# 3__Output_Feedback.net
KiCad netlist of a schematic drawn in Altium Designer
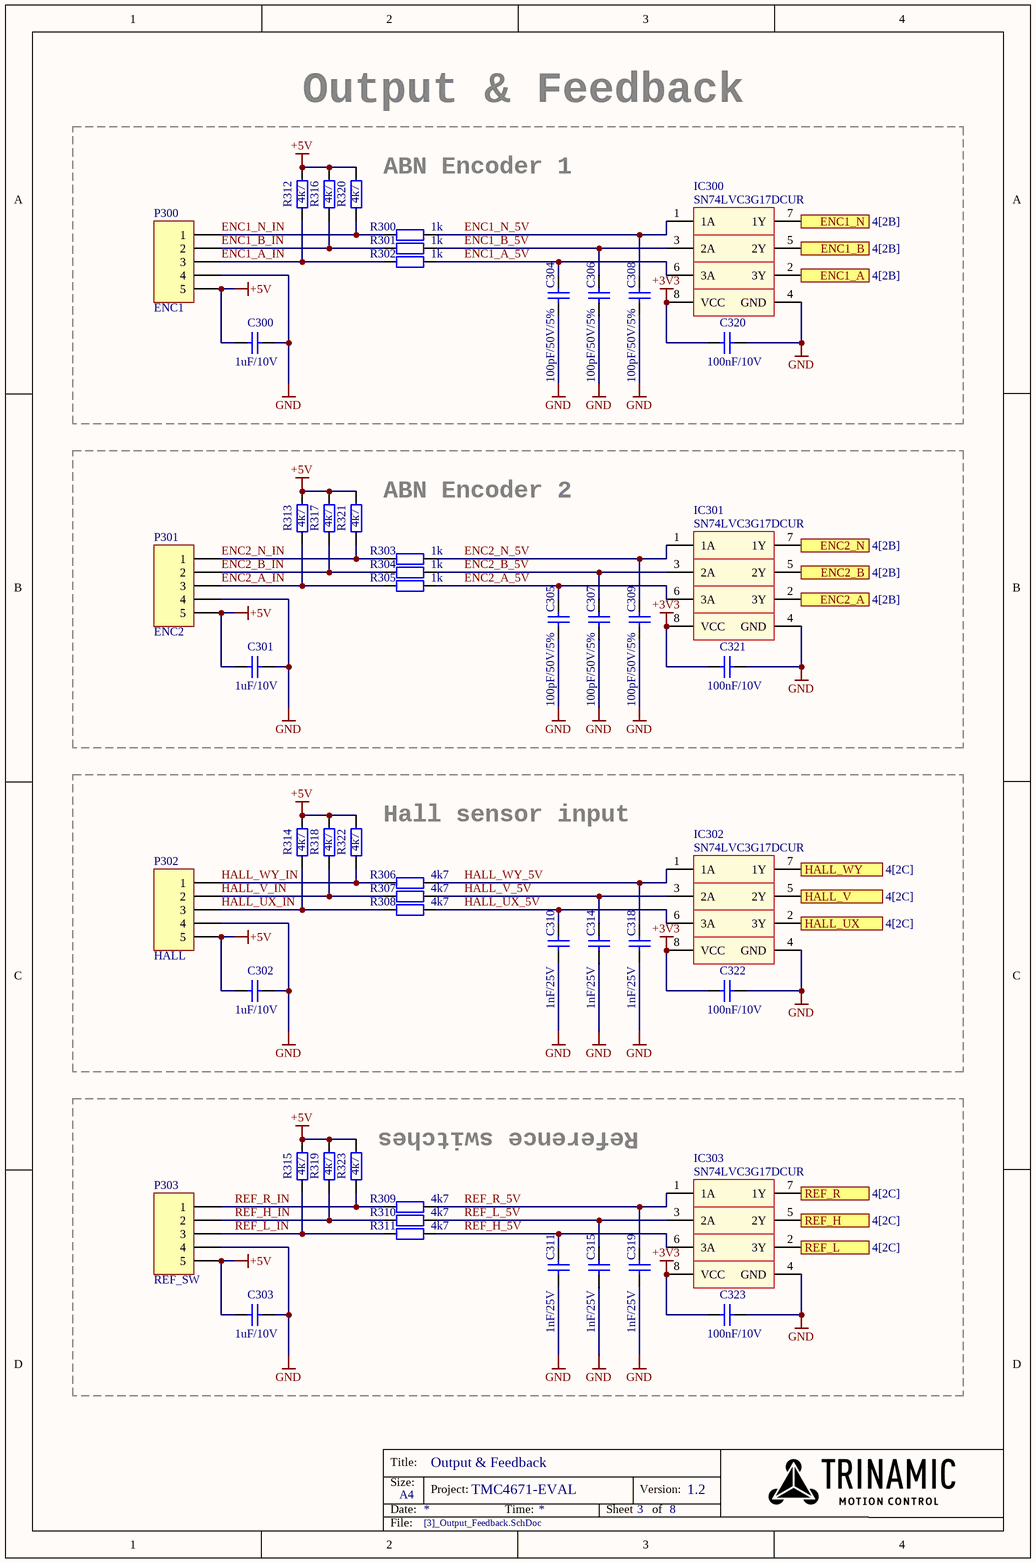
[diagram p0: [3]_Output_Feedback.SchDoc]

(export (version "E")
  (design (tool "Eeschema 10.0.6"))
  (components
    (comp (ref "C300")
      (value "1uF/10V")
      (footprint "C0603")
      (description "SMD Multilayer Ceramic Capacitor, 0603 [1608 Metric], 1 µF, 10 V, ± 10%, X5R, MC Series")
      (fields (field (name "MF") "MULTICOMP") (field (name "MPN") "MC0603X105K100CT"))
      (libsource (lib "SMD_Passives") (part "C, 1 µF, 10 V, ± 10%, X5R, MC Series, 0603 [1608 Metric]"))
    )
    (comp (ref "C301")
      (value "1uF/10V")
      (footprint "C0603")
      (description "SMD Multilayer Ceramic Capacitor, 0603 [1608 Metric], 1 µF, 10 V, ± 10%, X5R, MC Series")
      (fields (field (name "MF") "MULTICOMP") (field (name "MPN") "MC0603X105K100CT"))
      (libsource (lib "SMD_Passives") (part "C, 1 µF, 10 V, ± 10%, X5R, MC Series, 0603 [1608 Metric]"))
    )
    (comp (ref "C302")
      (value "1uF/10V")
      (footprint "C0603")
      (description "SMD Multilayer Ceramic Capacitor, 0603 [1608 Metric], 1 µF, 10 V, ± 10%, X5R, MC Series")
      (fields (field (name "MF") "MULTICOMP") (field (name "MPN") "MC0603X105K100CT"))
      (libsource (lib "SMD_Passives") (part "C, 1 µF, 10 V, ± 10%, X5R, MC Series, 0603 [1608 Metric]"))
    )
    (comp (ref "C303")
      (value "1uF/10V")
      (footprint "C0603")
      (description "SMD Multilayer Ceramic Capacitor, 0603 [1608 Metric], 1 µF, 10 V, ± 10%, X5R, MC Series")
      (fields (field (name "MF") "MULTICOMP") (field (name "MPN") "MC0603X105K100CT"))
      (libsource (lib "SMD_Passives") (part "C, 1 µF, 10 V, ± 10%, X5R, MC Series, 0603 [1608 Metric]"))
    )
    (comp (ref "C304")
      (value "100pF/50V/5%")
      (footprint "C0603")
      (description "SMD Multilayer Ceramic Capacitor, 0603 [1608 Metric], 100 pF, 50 V, ± 5%, C0G / NP0, MC Series")
      (fields (field (name "MF") "MULTICOMP") (field (name "MPN") "MC0603N101J500CT"))
      (libsource (lib "SMD_Passives") (part "C, 100 pF, 50 V, ± 5%, C0G / NP0, MC Series, 0603 [1608 Metric]"))
    )
    (comp (ref "C305")
      (value "100pF/50V/5%")
      (footprint "C0603")
      (description "SMD Multilayer Ceramic Capacitor, 0603 [1608 Metric], 100 pF, 50 V, ± 5%, C0G / NP0, MC Series")
      (fields (field (name "MF") "MULTICOMP") (field (name "MPN") "MC0603N101J500CT"))
      (libsource (lib "SMD_Passives") (part "C, 100 pF, 50 V, ± 5%, C0G / NP0, MC Series, 0603 [1608 Metric]"))
    )
    (comp (ref "C306")
      (value "100pF/50V/5%")
      (footprint "C0603")
      (description "SMD Multilayer Ceramic Capacitor, 0603 [1608 Metric], 100 pF, 50 V, ± 5%, C0G / NP0, MC Series")
      (fields (field (name "MF") "MULTICOMP") (field (name "MPN") "MC0603N101J500CT"))
      (libsource (lib "SMD_Passives") (part "C, 100 pF, 50 V, ± 5%, C0G / NP0, MC Series, 0603 [1608 Metric]"))
    )
    (comp (ref "C307")
      (value "100pF/50V/5%")
      (footprint "C0603")
      (description "SMD Multilayer Ceramic Capacitor, 0603 [1608 Metric], 100 pF, 50 V, ± 5%, C0G / NP0, MC Series")
      (fields (field (name "MF") "MULTICOMP") (field (name "MPN") "MC0603N101J500CT"))
      (libsource (lib "SMD_Passives") (part "C, 100 pF, 50 V, ± 5%, C0G / NP0, MC Series, 0603 [1608 Metric]"))
    )
    (comp (ref "C308")
      (value "100pF/50V/5%")
      (footprint "C0603")
      (description "SMD Multilayer Ceramic Capacitor, 0603 [1608 Metric], 100 pF, 50 V, ± 5%, C0G / NP0, MC Series")
      (fields (field (name "MF") "MULTICOMP") (field (name "MPN") "MC0603N101J500CT"))
      (libsource (lib "SMD_Passives") (part "C, 100 pF, 50 V, ± 5%, C0G / NP0, MC Series, 0603 [1608 Metric]"))
    )
    (comp (ref "C309")
      (value "100pF/50V/5%")
      (footprint "C0603")
      (description "SMD Multilayer Ceramic Capacitor, 0603 [1608 Metric], 100 pF, 50 V, ± 5%, C0G / NP0, MC Series")
      (fields (field (name "MF") "MULTICOMP") (field (name "MPN") "MC0603N101J500CT"))
      (libsource (lib "SMD_Passives") (part "C, 100 pF, 50 V, ± 5%, C0G / NP0, MC Series, 0603 [1608 Metric]"))
    )
    (comp (ref "C310")
      (value "1nF/25V")
      (footprint "C0603")
      (description "SMD Multilayer Ceramic Capacitor, 0603 [1608 Metric], 1000 pF, 25 V, ± 10%, X7R, MC Series")
      (fields (field (name "MF") "MULTICOMP") (field (name "MPN") "MC0603B102K250CT"))
      (libsource (lib "SMD_Passives") (part "C, 1nF, 25 V, ± 10%, X7R, MC Series, 0603 [1608 Metric]"))
    )
    (comp (ref "C311")
      (value "1nF/25V")
      (footprint "C0603")
      (description "SMD Multilayer Ceramic Capacitor, 0603 [1608 Metric], 1000 pF, 25 V, ± 10%, X7R, MC Series")
      (fields (field (name "MF") "MULTICOMP") (field (name "MPN") "MC0603B102K250CT"))
      (libsource (lib "SMD_Passives") (part "C, 1nF, 25 V, ± 10%, X7R, MC Series, 0603 [1608 Metric]"))
    )
    (comp (ref "C314")
      (value "1nF/25V")
      (footprint "C0603")
      (description "SMD Multilayer Ceramic Capacitor, 0603 [1608 Metric], 1000 pF, 25 V, ± 10%, X7R, MC Series")
      (fields (field (name "MF") "MULTICOMP") (field (name "MPN") "MC0603B102K250CT"))
      (libsource (lib "SMD_Passives") (part "C, 1nF, 25 V, ± 10%, X7R, MC Series, 0603 [1608 Metric]"))
    )
    (comp (ref "C315")
      (value "1nF/25V")
      (footprint "C0603")
      (description "SMD Multilayer Ceramic Capacitor, 0603 [1608 Metric], 1000 pF, 25 V, ± 10%, X7R, MC Series")
      (fields (field (name "MF") "MULTICOMP") (field (name "MPN") "MC0603B102K250CT"))
      (libsource (lib "SMD_Passives") (part "C, 1nF, 25 V, ± 10%, X7R, MC Series, 0603 [1608 Metric]"))
    )
    (comp (ref "C318")
      (value "1nF/25V")
      (footprint "C0603")
      (description "SMD Multilayer Ceramic Capacitor, 0603 [1608 Metric], 1000 pF, 25 V, ± 10%, X7R, MC Series")
      (fields (field (name "MF") "MULTICOMP") (field (name "MPN") "MC0603B102K250CT"))
      (libsource (lib "SMD_Passives") (part "C, 1nF, 25 V, ± 10%, X7R, MC Series, 0603 [1608 Metric]"))
    )
    (comp (ref "C319")
      (value "1nF/25V")
      (footprint "C0603")
      (description "SMD Multilayer Ceramic Capacitor, 0603 [1608 Metric], 1000 pF, 25 V, ± 10%, X7R, MC Series")
      (fields (field (name "MF") "MULTICOMP") (field (name "MPN") "MC0603B102K250CT"))
      (libsource (lib "SMD_Passives") (part "C, 1nF, 25 V, ± 10%, X7R, MC Series, 0603 [1608 Metric]"))
    )
    (comp (ref "C320")
      (value "100nF/10V")
      (footprint "C0603")
      (description "SMD Multilayer Ceramic Capacitor, 0603 [1608 Metric], 0.1 µF, 10 V, ± 10%, X7R, MC Series")
      (fields (field (name "MF") "Multicomp") (field (name "MPN") "MC0603B104K100CT"))
      (libsource (lib "SMD_Passives") (part "C, 0.1 µF, 10 V, ± 10%, X7R, 0603"))
    )
    (comp (ref "C321")
      (value "100nF/10V")
      (footprint "C0603")
      (description "SMD Multilayer Ceramic Capacitor, 0603 [1608 Metric], 0.1 µF, 10 V, ± 10%, X7R, MC Series")
      (fields (field (name "MF") "Multicomp") (field (name "MPN") "MC0603B104K100CT"))
      (libsource (lib "SMD_Passives") (part "C, 0.1 µF, 10 V, ± 10%, X7R, 0603"))
    )
    (comp (ref "C322")
      (value "100nF/10V")
      (footprint "C0603")
      (description "SMD Multilayer Ceramic Capacitor, 0603 [1608 Metric], 0.1 µF, 10 V, ± 10%, X7R, MC Series")
      (fields (field (name "MF") "Multicomp") (field (name "MPN") "MC0603B104K100CT"))
      (libsource (lib "SMD_Passives") (part "C, 0.1 µF, 10 V, ± 10%, X7R, 0603"))
    )
    (comp (ref "C323")
      (value "100nF/10V")
      (footprint "C0603")
      (description "SMD Multilayer Ceramic Capacitor, 0603 [1608 Metric], 0.1 µF, 10 V, ± 10%, X7R, MC Series")
      (fields (field (name "MF") "Multicomp") (field (name "MPN") "MC0603B104K100CT"))
      (libsource (lib "SMD_Passives") (part "C, 0.1 µF, 10 V, ± 10%, X7R, 0603"))
    )
    (comp (ref "IC300")
      (value "SN74LVC3G17DCUR")
      (footprint "TSSOP50P310X90-8L")
      (description "Triple Schmitt-Trigger Buffer, 74LVC3G17, 1.65 V to 5.5 V, VSSOP-8")
      (fields (field (name "MF") "TEXAS INSTRUMENTS"))
      (libsource (lib "TMC4671-EVAL_V1_0") (part "SN74LVC3G17DCUR"))
    )
    (comp (ref "IC301")
      (value "SN74LVC3G17DCUR")
      (footprint "TSSOP50P310X90-8L")
      (description "Triple Schmitt-Trigger Buffer, 74LVC3G17, 1.65 V to 5.5 V, VSSOP-8")
      (fields (field (name "MF") "TEXAS INSTRUMENTS"))
      (libsource (lib "TMC4671-EVAL_V1_0") (part "SN74LVC3G17DCUR"))
    )
    (comp (ref "IC302")
      (value "SN74LVC3G17DCUR")
      (footprint "TSSOP50P310X90-8L")
      (description "Triple Schmitt-Trigger Buffer, 74LVC3G17, 1.65 V to 5.5 V, VSSOP-8")
      (fields (field (name "MF") "TEXAS INSTRUMENTS"))
      (libsource (lib "TMC4671-EVAL_V1_0") (part "SN74LVC3G17DCUR"))
    )
    (comp (ref "IC303")
      (value "SN74LVC3G17DCUR")
      (footprint "TSSOP50P310X90-8L")
      (description "Triple Schmitt-Trigger Buffer, 74LVC3G17, 1.65 V to 5.5 V, VSSOP-8")
      (fields (field (name "MF") "TEXAS INSTRUMENTS"))
      (libsource (lib "TMC4671-EVAL_V1_0") (part "SN74LVC3G17DCUR"))
    )
    (comp (ref "P300")
      (value "ENC1")
      (footprint "TH_HDR_1X5")
      (description "Header, 5-Pin")
      (libsource (lib "Miscellaneous Connectors") (part "Header 5"))
    )
    (comp (ref "P301")
      (value "ENC2")
      (footprint "TH_HDR_1X5")
      (description "Header, 5-Pin")
      (libsource (lib "Miscellaneous Connectors") (part "Header 5"))
    )
    (comp (ref "P302")
      (value "HALL")
      (footprint "TH_HDR_1X5")
      (description "Header, 5-Pin")
      (libsource (lib "Miscellaneous Connectors") (part "Header 5"))
    )
    (comp (ref "P303")
      (value "REF_SW")
      (footprint "TH_HDR_1X5")
      (description "Header, 5-Pin")
      (libsource (lib "Miscellaneous Connectors") (part "Header 5"))
    )
    (comp (ref "R300")
      (value "1k")
      (footprint "R0603")
      (description "SMD Chip Resistor, Thick Film, 1 kohm, 50 V, 0603 [1608 Metric], 100 mW, ± 1%, MCWR Series")
      (fields
        (field (name "MPN") "MCWR06X1001FTL")
        (field (name "MF") "MULTICOMP")
        (field (name "RESISTANCE") "1k")
      )
      (libsource (lib "SMD_Passives") (part "R, 1 kohm, 50 V, 0603 [1608 Metric], 100mW, ± 1%, MCWR Series"))
    )
    (comp (ref "R301")
      (value "1k")
      (footprint "R0603")
      (description "SMD Chip Resistor, Thick Film, 1 kohm, 50 V, 0603 [1608 Metric], 100 mW, ± 1%, MCWR Series")
      (fields
        (field (name "MPN") "MCWR06X1001FTL")
        (field (name "MF") "MULTICOMP")
        (field (name "RESISTANCE") "1k")
      )
      (libsource (lib "SMD_Passives") (part "R, 1 kohm, 50 V, 0603 [1608 Metric], 100mW, ± 1%, MCWR Series"))
    )
    (comp (ref "R302")
      (value "1k")
      (footprint "R0603")
      (description "SMD Chip Resistor, Thick Film, 1 kohm, 50 V, 0603 [1608 Metric], 100 mW, ± 1%, MCWR Series")
      (fields
        (field (name "MPN") "MCWR06X1001FTL")
        (field (name "MF") "MULTICOMP")
        (field (name "RESISTANCE") "1k")
      )
      (libsource (lib "SMD_Passives") (part "R, 1 kohm, 50 V, 0603 [1608 Metric], 100mW, ± 1%, MCWR Series"))
    )
    (comp (ref "R303")
      (value "1k")
      (footprint "R0603")
      (description "SMD Chip Resistor, Thick Film, 1 kohm, 50 V, 0603 [1608 Metric], 100 mW, ± 1%, MCWR Series")
      (fields
        (field (name "MPN") "MCWR06X1001FTL")
        (field (name "MF") "MULTICOMP")
        (field (name "RESISTANCE") "1k")
      )
      (libsource (lib "SMD_Passives") (part "R, 1 kohm, 50 V, 0603 [1608 Metric], 100mW, ± 1%, MCWR Series"))
    )
    (comp (ref "R304")
      (value "1k")
      (footprint "R0603")
      (description "SMD Chip Resistor, Thick Film, 1 kohm, 50 V, 0603 [1608 Metric], 100 mW, ± 1%, MCWR Series")
      (fields
        (field (name "MPN") "MCWR06X1001FTL")
        (field (name "MF") "MULTICOMP")
        (field (name "RESISTANCE") "1k")
      )
      (libsource (lib "SMD_Passives") (part "R, 1 kohm, 50 V, 0603 [1608 Metric], 100mW, ± 1%, MCWR Series"))
    )
    (comp (ref "R305")
      (value "1k")
      (footprint "R0603")
      (description "SMD Chip Resistor, Thick Film, 1 kohm, 50 V, 0603 [1608 Metric], 100 mW, ± 1%, MCWR Series")
      (fields
        (field (name "MPN") "MCWR06X1001FTL")
        (field (name "MF") "MULTICOMP")
        (field (name "RESISTANCE") "1k")
      )
      (libsource (lib "SMD_Passives") (part "R, 1 kohm, 50 V, 0603 [1608 Metric], 100mW, ± 1%, MCWR Series"))
    )
    (comp (ref "R306")
      (value "4k7")
      (footprint "R0603")
      (description "SMD Chip Resistor, 4.7 kohm, 75 V, 0603 [1608 Metric], 100 mW, ± 1%, WR06 Series")
      (fields
        (field (name "MPN") "WR06X4701FTL")
        (field (name "MF") "WALSIN")
        (field (name "RESISTANCE") "4k7")
      )
      (libsource (lib "SMD_Passives") (part "R, 4.7 kohm, 75 V, 0603 [1608 Metric], 100 mW, ± 1%, WR06 Series"))
    )
    (comp (ref "R307")
      (value "4k7")
      (footprint "R0603")
      (description "SMD Chip Resistor, 4.7 kohm, 75 V, 0603 [1608 Metric], 100 mW, ± 1%, WR06 Series")
      (fields
        (field (name "MPN") "WR06X4701FTL")
        (field (name "MF") "WALSIN")
        (field (name "RESISTANCE") "4k7")
      )
      (libsource (lib "SMD_Passives") (part "R, 4.7 kohm, 75 V, 0603 [1608 Metric], 100 mW, ± 1%, WR06 Series"))
    )
    (comp (ref "R308")
      (value "4k7")
      (footprint "R0603")
      (description "SMD Chip Resistor, 4.7 kohm, 75 V, 0603 [1608 Metric], 100 mW, ± 1%, WR06 Series")
      (fields
        (field (name "MPN") "WR06X4701FTL")
        (field (name "MF") "WALSIN")
        (field (name "RESISTANCE") "4k7")
      )
      (libsource (lib "SMD_Passives") (part "R, 4.7 kohm, 75 V, 0603 [1608 Metric], 100 mW, ± 1%, WR06 Series"))
    )
    (comp (ref "R309")
      (value "4k7")
      (footprint "R0603")
      (description "SMD Chip Resistor, 4.7 kohm, 75 V, 0603 [1608 Metric], 100 mW, ± 1%, WR06 Series")
      (fields
        (field (name "MPN") "WR06X4701FTL")
        (field (name "MF") "WALSIN")
        (field (name "RESISTANCE") "4k7")
      )
      (libsource (lib "SMD_Passives") (part "R, 4.7 kohm, 75 V, 0603 [1608 Metric], 100 mW, ± 1%, WR06 Series"))
    )
    (comp (ref "R310")
      (value "4k7")
      (footprint "R0603")
      (description "SMD Chip Resistor, 4.7 kohm, 75 V, 0603 [1608 Metric], 100 mW, ± 1%, WR06 Series")
      (fields
        (field (name "MPN") "WR06X4701FTL")
        (field (name "MF") "WALSIN")
        (field (name "RESISTANCE") "4k7")
      )
      (libsource (lib "SMD_Passives") (part "R, 4.7 kohm, 75 V, 0603 [1608 Metric], 100 mW, ± 1%, WR06 Series"))
    )
    (comp (ref "R311")
      (value "4k7")
      (footprint "R0603")
      (description "SMD Chip Resistor, 4.7 kohm, 75 V, 0603 [1608 Metric], 100 mW, ± 1%, WR06 Series")
      (fields
        (field (name "MPN") "WR06X4701FTL")
        (field (name "MF") "WALSIN")
        (field (name "RESISTANCE") "4k7")
      )
      (libsource (lib "SMD_Passives") (part "R, 4.7 kohm, 75 V, 0603 [1608 Metric], 100 mW, ± 1%, WR06 Series"))
    )
    (comp (ref "R312")
      (value "4k7")
      (footprint "R0603")
      (description "SMD Chip Resistor, 4.7 kohm, 75 V, 0603 [1608 Metric], 100 mW, ± 1%, WR06 Series")
      (fields
        (field (name "MPN") "WR06X4701FTL")
        (field (name "MF") "WALSIN")
        (field (name "RESISTANCE") "4k7")
      )
      (libsource (lib "") (part "R, 4.7 kohm, 75 V, 0603 [1608 Metric], 100 mW, ± 1%, WR06 Series_1"))
    )
    (comp (ref "R313")
      (value "4k7")
      (footprint "R0603")
      (description "SMD Chip Resistor, 4.7 kohm, 75 V, 0603 [1608 Metric], 100 mW, ± 1%, WR06 Series")
      (fields
        (field (name "MPN") "WR06X4701FTL")
        (field (name "MF") "WALSIN")
        (field (name "RESISTANCE") "4k7")
      )
      (libsource (lib "") (part "R, 4.7 kohm, 75 V, 0603 [1608 Metric], 100 mW, ± 1%, WR06 Series_1"))
    )
    (comp (ref "R314")
      (value "4k7")
      (footprint "R0603")
      (description "SMD Chip Resistor, 4.7 kohm, 75 V, 0603 [1608 Metric], 100 mW, ± 1%, WR06 Series")
      (fields
        (field (name "MPN") "WR06X4701FTL")
        (field (name "MF") "WALSIN")
        (field (name "RESISTANCE") "4k7")
      )
      (libsource (lib "") (part "R, 4.7 kohm, 75 V, 0603 [1608 Metric], 100 mW, ± 1%, WR06 Series_1"))
    )
    (comp (ref "R315")
      (value "4k7")
      (footprint "R0603")
      (description "SMD Chip Resistor, 4.7 kohm, 75 V, 0603 [1608 Metric], 100 mW, ± 1%, WR06 Series")
      (fields
        (field (name "MPN") "WR06X4701FTL")
        (field (name "MF") "WALSIN")
        (field (name "RESISTANCE") "4k7")
      )
      (libsource (lib "") (part "R, 4.7 kohm, 75 V, 0603 [1608 Metric], 100 mW, ± 1%, WR06 Series_1"))
    )
    (comp (ref "R316")
      (value "4k7")
      (footprint "R0603")
      (description "SMD Chip Resistor, 4.7 kohm, 75 V, 0603 [1608 Metric], 100 mW, ± 1%, WR06 Series")
      (fields
        (field (name "MPN") "WR06X4701FTL")
        (field (name "MF") "WALSIN")
        (field (name "RESISTANCE") "4k7")
      )
      (libsource (lib "") (part "R, 4.7 kohm, 75 V, 0603 [1608 Metric], 100 mW, ± 1%, WR06 Series_1"))
    )
    (comp (ref "R317")
      (value "4k7")
      (footprint "R0603")
      (description "SMD Chip Resistor, 4.7 kohm, 75 V, 0603 [1608 Metric], 100 mW, ± 1%, WR06 Series")
      (fields
        (field (name "MPN") "WR06X4701FTL")
        (field (name "MF") "WALSIN")
        (field (name "RESISTANCE") "4k7")
      )
      (libsource (lib "") (part "R, 4.7 kohm, 75 V, 0603 [1608 Metric], 100 mW, ± 1%, WR06 Series_1"))
    )
    (comp (ref "R318")
      (value "4k7")
      (footprint "R0603")
      (description "SMD Chip Resistor, 4.7 kohm, 75 V, 0603 [1608 Metric], 100 mW, ± 1%, WR06 Series")
      (fields
        (field (name "MPN") "WR06X4701FTL")
        (field (name "MF") "WALSIN")
        (field (name "RESISTANCE") "4k7")
      )
      (libsource (lib "") (part "R, 4.7 kohm, 75 V, 0603 [1608 Metric], 100 mW, ± 1%, WR06 Series_1"))
    )
    (comp (ref "R319")
      (value "4k7")
      (footprint "R0603")
      (description "SMD Chip Resistor, 4.7 kohm, 75 V, 0603 [1608 Metric], 100 mW, ± 1%, WR06 Series")
      (fields
        (field (name "MPN") "WR06X4701FTL")
        (field (name "MF") "WALSIN")
        (field (name "RESISTANCE") "4k7")
      )
      (libsource (lib "") (part "R, 4.7 kohm, 75 V, 0603 [1608 Metric], 100 mW, ± 1%, WR06 Series_1"))
    )
    (comp (ref "R320")
      (value "4k7")
      (footprint "R0603")
      (description "SMD Chip Resistor, 4.7 kohm, 75 V, 0603 [1608 Metric], 100 mW, ± 1%, WR06 Series")
      (fields
        (field (name "MPN") "WR06X4701FTL")
        (field (name "MF") "WALSIN")
        (field (name "RESISTANCE") "4k7")
      )
      (libsource (lib "") (part "R, 4.7 kohm, 75 V, 0603 [1608 Metric], 100 mW, ± 1%, WR06 Series_1"))
    )
    (comp (ref "R321")
      (value "4k7")
      (footprint "R0603")
      (description "SMD Chip Resistor, 4.7 kohm, 75 V, 0603 [1608 Metric], 100 mW, ± 1%, WR06 Series")
      (fields
        (field (name "MPN") "WR06X4701FTL")
        (field (name "MF") "WALSIN")
        (field (name "RESISTANCE") "4k7")
      )
      (libsource (lib "") (part "R, 4.7 kohm, 75 V, 0603 [1608 Metric], 100 mW, ± 1%, WR06 Series_1"))
    )
    (comp (ref "R322")
      (value "4k7")
      (footprint "R0603")
      (description "SMD Chip Resistor, 4.7 kohm, 75 V, 0603 [1608 Metric], 100 mW, ± 1%, WR06 Series")
      (fields
        (field (name "MPN") "WR06X4701FTL")
        (field (name "MF") "WALSIN")
        (field (name "RESISTANCE") "4k7")
      )
      (libsource (lib "") (part "R, 4.7 kohm, 75 V, 0603 [1608 Metric], 100 mW, ± 1%, WR06 Series_1"))
    )
    (comp (ref "R323")
      (value "4k7")
      (footprint "R0603")
      (description "SMD Chip Resistor, 4.7 kohm, 75 V, 0603 [1608 Metric], 100 mW, ± 1%, WR06 Series")
      (fields
        (field (name "MPN") "WR06X4701FTL")
        (field (name "MF") "WALSIN")
        (field (name "RESISTANCE") "4k7")
      )
      (libsource (lib "") (part "R, 4.7 kohm, 75 V, 0603 [1608 Metric], 100 mW, ± 1%, WR06 Series_1"))
    )
  )
  (nets
    (net (code "1") (name "+3V3") (class "Default")
      (node (ref "C320") (pin "2") (pinfunction "2_2") (pintype "passive"))
      (node (ref "C321") (pin "2") (pinfunction "2_2") (pintype "passive"))
      (node (ref "C322") (pin "2") (pinfunction "2_2") (pintype "passive"))
      (node (ref "C323") (pin "2") (pinfunction "2_2") (pintype "passive"))
      (node (ref "IC300") (pin "8") (pinfunction "VCC_8") (pintype "power_in"))
      (node (ref "IC301") (pin "8") (pinfunction "VCC_8") (pintype "power_in"))
      (node (ref "IC302") (pin "8") (pinfunction "VCC_8") (pintype "power_in"))
      (node (ref "IC303") (pin "8") (pinfunction "VCC_8") (pintype "power_in"))
    )
    (net (code "2") (name "+5V") (class "Default")
      (node (ref "C300") (pin "2") (pinfunction "2_2") (pintype "passive"))
      (node (ref "C301") (pin "2") (pinfunction "2_2") (pintype "passive"))
      (node (ref "C302") (pin "2") (pinfunction "2_2") (pintype "passive"))
      (node (ref "C303") (pin "2") (pinfunction "2_2") (pintype "passive"))
      (node (ref "P300") (pin "5") (pinfunction "5_5") (pintype "passive"))
      (node (ref "P301") (pin "5") (pinfunction "5_5") (pintype "passive"))
      (node (ref "P302") (pin "5") (pinfunction "5_5") (pintype "passive"))
      (node (ref "P303") (pin "5") (pinfunction "5_5") (pintype "passive"))
      (node (ref "R312") (pin "2") (pinfunction "2_2") (pintype "passive"))
      (node (ref "R313") (pin "2") (pinfunction "2_2") (pintype "passive"))
      (node (ref "R314") (pin "2") (pinfunction "2_2") (pintype "passive"))
      (node (ref "R315") (pin "2") (pinfunction "2_2") (pintype "passive"))
      (node (ref "R316") (pin "2") (pinfunction "2_2") (pintype "passive"))
      (node (ref "R317") (pin "2") (pinfunction "2_2") (pintype "passive"))
      (node (ref "R318") (pin "2") (pinfunction "2_2") (pintype "passive"))
      (node (ref "R319") (pin "2") (pinfunction "2_2") (pintype "passive"))
      (node (ref "R320") (pin "2") (pinfunction "2_2") (pintype "passive"))
      (node (ref "R321") (pin "2") (pinfunction "2_2") (pintype "passive"))
      (node (ref "R322") (pin "2") (pinfunction "2_2") (pintype "passive"))
      (node (ref "R323") (pin "2") (pinfunction "2_2") (pintype "passive"))
    )
    (net (code "3") (name "/ENC1_A") (class "Default")
      (node (ref "IC300") (pin "2") (pinfunction "3Y_2") (pintype "power_in"))
    )
    (net (code "4") (name "/ENC1_A_5V") (class "Default")
      (node (ref "C304") (pin "2") (pinfunction "2_2") (pintype "passive"))
      (node (ref "IC300") (pin "6") (pinfunction "3A_6") (pintype "power_in"))
      (node (ref "R302") (pin "2") (pinfunction "2_2") (pintype "passive"))
    )
    (net (code "5") (name "/ENC1_A_IN") (class "Default")
      (node (ref "P300") (pin "3") (pinfunction "3_3") (pintype "passive"))
      (node (ref "R302") (pin "1") (pinfunction "1_1") (pintype "passive"))
      (node (ref "R312") (pin "1") (pinfunction "1_1") (pintype "passive"))
    )
    (net (code "6") (name "/ENC1_B") (class "Default")
      (node (ref "IC300") (pin "5") (pinfunction "2Y_5") (pintype "power_in"))
    )
    (net (code "7") (name "/ENC1_B_5V") (class "Default")
      (node (ref "C306") (pin "2") (pinfunction "2_2") (pintype "passive"))
      (node (ref "IC300") (pin "3") (pinfunction "2A_3") (pintype "power_in"))
      (node (ref "R301") (pin "2") (pinfunction "2_2") (pintype "passive"))
    )
    (net (code "8") (name "/ENC1_B_IN") (class "Default")
      (node (ref "P300") (pin "2") (pinfunction "2_2") (pintype "passive"))
      (node (ref "R301") (pin "1") (pinfunction "1_1") (pintype "passive"))
      (node (ref "R316") (pin "1") (pinfunction "1_1") (pintype "passive"))
    )
    (net (code "9") (name "/ENC1_N") (class "Default")
      (node (ref "IC300") (pin "7") (pinfunction "1Y_7") (pintype "power_in"))
    )
    (net (code "10") (name "/ENC1_N_5V") (class "Default")
      (node (ref "C308") (pin "2") (pinfunction "2_2") (pintype "passive"))
      (node (ref "IC300") (pin "1") (pinfunction "1A_1") (pintype "power_in"))
      (node (ref "R300") (pin "2") (pinfunction "2_2") (pintype "passive"))
    )
    (net (code "11") (name "/ENC1_N_IN") (class "Default")
      (node (ref "P300") (pin "1") (pinfunction "1_1") (pintype "passive"))
      (node (ref "R300") (pin "1") (pinfunction "1_1") (pintype "passive"))
      (node (ref "R320") (pin "1") (pinfunction "1_1") (pintype "passive"))
    )
    (net (code "12") (name "/ENC2_A") (class "Default")
      (node (ref "IC301") (pin "2") (pinfunction "3Y_2") (pintype "power_in"))
    )
    (net (code "13") (name "/ENC2_A_5V") (class "Default")
      (node (ref "C305") (pin "2") (pinfunction "2_2") (pintype "passive"))
      (node (ref "IC301") (pin "6") (pinfunction "3A_6") (pintype "power_in"))
      (node (ref "R305") (pin "2") (pinfunction "2_2") (pintype "passive"))
    )
    (net (code "14") (name "/ENC2_A_IN") (class "Default")
      (node (ref "P301") (pin "3") (pinfunction "3_3") (pintype "passive"))
      (node (ref "R305") (pin "1") (pinfunction "1_1") (pintype "passive"))
      (node (ref "R313") (pin "1") (pinfunction "1_1") (pintype "passive"))
    )
    (net (code "15") (name "/ENC2_B") (class "Default")
      (node (ref "IC301") (pin "5") (pinfunction "2Y_5") (pintype "power_in"))
    )
    (net (code "16") (name "/ENC2_B_5V") (class "Default")
      (node (ref "C307") (pin "2") (pinfunction "2_2") (pintype "passive"))
      (node (ref "IC301") (pin "3") (pinfunction "2A_3") (pintype "power_in"))
      (node (ref "R304") (pin "2") (pinfunction "2_2") (pintype "passive"))
    )
    (net (code "17") (name "/ENC2_B_IN") (class "Default")
      (node (ref "P301") (pin "2") (pinfunction "2_2") (pintype "passive"))
      (node (ref "R304") (pin "1") (pinfunction "1_1") (pintype "passive"))
      (node (ref "R317") (pin "1") (pinfunction "1_1") (pintype "passive"))
    )
    (net (code "18") (name "/ENC2_N") (class "Default")
      (node (ref "IC301") (pin "7") (pinfunction "1Y_7") (pintype "power_in"))
    )
    (net (code "19") (name "/ENC2_N_5V") (class "Default")
      (node (ref "C309") (pin "2") (pinfunction "2_2") (pintype "passive"))
      (node (ref "IC301") (pin "1") (pinfunction "1A_1") (pintype "power_in"))
      (node (ref "R303") (pin "2") (pinfunction "2_2") (pintype "passive"))
    )
    (net (code "20") (name "/ENC2_N_IN") (class "Default")
      (node (ref "P301") (pin "1") (pinfunction "1_1") (pintype "passive"))
      (node (ref "R303") (pin "1") (pinfunction "1_1") (pintype "passive"))
      (node (ref "R321") (pin "1") (pinfunction "1_1") (pintype "passive"))
    )
    (net (code "21") (name "/HALL_UX") (class "Default")
      (node (ref "IC302") (pin "2") (pinfunction "3Y_2") (pintype "power_in"))
    )
    (net (code "22") (name "/HALL_UX_5V") (class "Default")
      (node (ref "C310") (pin "2") (pinfunction "2_2") (pintype "passive"))
      (node (ref "IC302") (pin "6") (pinfunction "3A_6") (pintype "power_in"))
      (node (ref "R308") (pin "1") (pinfunction "1_1") (pintype "passive"))
    )
    (net (code "23") (name "/HALL_UX_IN") (class "Default")
      (node (ref "P302") (pin "3") (pinfunction "3_3") (pintype "passive"))
      (node (ref "R308") (pin "2") (pinfunction "2_2") (pintype "passive"))
      (node (ref "R314") (pin "1") (pinfunction "1_1") (pintype "passive"))
    )
    (net (code "24") (name "/HALL_V") (class "Default")
      (node (ref "IC302") (pin "5") (pinfunction "2Y_5") (pintype "power_in"))
    )
    (net (code "25") (name "/HALL_V_5V") (class "Default")
      (node (ref "C314") (pin "2") (pinfunction "2_2") (pintype "passive"))
      (node (ref "IC302") (pin "3") (pinfunction "2A_3") (pintype "power_in"))
      (node (ref "R307") (pin "1") (pinfunction "1_1") (pintype "passive"))
    )
    (net (code "26") (name "/HALL_V_IN") (class "Default")
      (node (ref "P302") (pin "2") (pinfunction "2_2") (pintype "passive"))
      (node (ref "R307") (pin "2") (pinfunction "2_2") (pintype "passive"))
      (node (ref "R318") (pin "1") (pinfunction "1_1") (pintype "passive"))
    )
    (net (code "27") (name "/HALL_WY") (class "Default")
      (node (ref "IC302") (pin "7") (pinfunction "1Y_7") (pintype "power_in"))
    )
    (net (code "28") (name "/HALL_WY_5V") (class "Default")
      (node (ref "C318") (pin "2") (pinfunction "2_2") (pintype "passive"))
      (node (ref "IC302") (pin "1") (pinfunction "1A_1") (pintype "power_in"))
      (node (ref "R306") (pin "1") (pinfunction "1_1") (pintype "passive"))
    )
    (net (code "29") (name "/HALL_WY_IN") (class "Default")
      (node (ref "P302") (pin "1") (pinfunction "1_1") (pintype "passive"))
      (node (ref "R306") (pin "2") (pinfunction "2_2") (pintype "passive"))
      (node (ref "R322") (pin "1") (pinfunction "1_1") (pintype "passive"))
    )
    (net (code "30") (name "/REF_H") (class "Default")
      (node (ref "IC303") (pin "5") (pinfunction "2Y_5") (pintype "power_in"))
    )
    (net (code "31") (name "/REF_H_5V") (class "Default")
      (node (ref "C311") (pin "2") (pinfunction "2_2") (pintype "passive"))
      (node (ref "IC303") (pin "6") (pinfunction "3A_6") (pintype "power_in"))
      (node (ref "R311") (pin "1") (pinfunction "1_1") (pintype "passive"))
    )
    (net (code "32") (name "/REF_H_IN") (class "Default")
      (node (ref "P303") (pin "2") (pinfunction "2_2") (pintype "passive"))
      (node (ref "R310") (pin "2") (pinfunction "2_2") (pintype "passive"))
      (node (ref "R319") (pin "1") (pinfunction "1_1") (pintype "passive"))
    )
    (net (code "33") (name "/REF_L") (class "Default")
      (node (ref "IC303") (pin "2") (pinfunction "3Y_2") (pintype "power_in"))
    )
    (net (code "34") (name "/REF_L_5V") (class "Default")
      (node (ref "C315") (pin "2") (pinfunction "2_2") (pintype "passive"))
      (node (ref "IC303") (pin "3") (pinfunction "2A_3") (pintype "power_in"))
      (node (ref "R310") (pin "1") (pinfunction "1_1") (pintype "passive"))
    )
    (net (code "35") (name "/REF_L_IN") (class "Default")
      (node (ref "P303") (pin "3") (pinfunction "3_3") (pintype "passive"))
      (node (ref "R311") (pin "2") (pinfunction "2_2") (pintype "passive"))
      (node (ref "R315") (pin "1") (pinfunction "1_1") (pintype "passive"))
    )
    (net (code "36") (name "/REF_R") (class "Default")
      (node (ref "IC303") (pin "7") (pinfunction "1Y_7") (pintype "power_in"))
    )
    (net (code "37") (name "/REF_R_5V") (class "Default")
      (node (ref "C319") (pin "2") (pinfunction "2_2") (pintype "passive"))
      (node (ref "IC303") (pin "1") (pinfunction "1A_1") (pintype "power_in"))
      (node (ref "R309") (pin "1") (pinfunction "1_1") (pintype "passive"))
    )
    (net (code "38") (name "/REF_R_IN") (class "Default")
      (node (ref "P303") (pin "1") (pinfunction "1_1") (pintype "passive"))
      (node (ref "R309") (pin "2") (pinfunction "2_2") (pintype "passive"))
      (node (ref "R323") (pin "1") (pinfunction "1_1") (pintype "passive"))
    )
    (net (code "39") (name "GND") (class "Default")
      (node (ref "C300") (pin "1") (pinfunction "1_1") (pintype "passive"))
      (node (ref "C301") (pin "1") (pinfunction "1_1") (pintype "passive"))
      (node (ref "C302") (pin "1") (pinfunction "1_1") (pintype "passive"))
      (node (ref "C303") (pin "1") (pinfunction "1_1") (pintype "passive"))
      (node (ref "C304") (pin "1") (pinfunction "1_1") (pintype "passive"))
      (node (ref "C305") (pin "1") (pinfunction "1_1") (pintype "passive"))
      (node (ref "C306") (pin "1") (pinfunction "1_1") (pintype "passive"))
      (node (ref "C307") (pin "1") (pinfunction "1_1") (pintype "passive"))
      (node (ref "C308") (pin "1") (pinfunction "1_1") (pintype "passive"))
      (node (ref "C309") (pin "1") (pinfunction "1_1") (pintype "passive"))
      (node (ref "C310") (pin "1") (pinfunction "1_1") (pintype "passive"))
      (node (ref "C311") (pin "1") (pinfunction "1_1") (pintype "passive"))
      (node (ref "C314") (pin "1") (pinfunction "1_1") (pintype "passive"))
      (node (ref "C315") (pin "1") (pinfunction "1_1") (pintype "passive"))
      (node (ref "C318") (pin "1") (pinfunction "1_1") (pintype "passive"))
      (node (ref "C319") (pin "1") (pinfunction "1_1") (pintype "passive"))
      (node (ref "C320") (pin "1") (pinfunction "1_1") (pintype "passive"))
      (node (ref "C321") (pin "1") (pinfunction "1_1") (pintype "passive"))
      (node (ref "C322") (pin "1") (pinfunction "1_1") (pintype "passive"))
      (node (ref "C323") (pin "1") (pinfunction "1_1") (pintype "passive"))
      (node (ref "IC300") (pin "4") (pinfunction "GND_4") (pintype "power_in"))
      (node (ref "IC301") (pin "4") (pinfunction "GND_4") (pintype "power_in"))
      (node (ref "IC302") (pin "4") (pinfunction "GND_4") (pintype "power_in"))
      (node (ref "IC303") (pin "4") (pinfunction "GND_4") (pintype "power_in"))
      (node (ref "P300") (pin "4") (pinfunction "4_4") (pintype "passive"))
      (node (ref "P301") (pin "4") (pinfunction "4_4") (pintype "passive"))
      (node (ref "P302") (pin "4") (pinfunction "4_4") (pintype "passive"))
      (node (ref "P303") (pin "4") (pinfunction "4_4") (pintype "passive"))
    )
  )
)
